# Main_Schematic_ScamAway.net
KiCad netlist of a schematic drawn in EAGLE
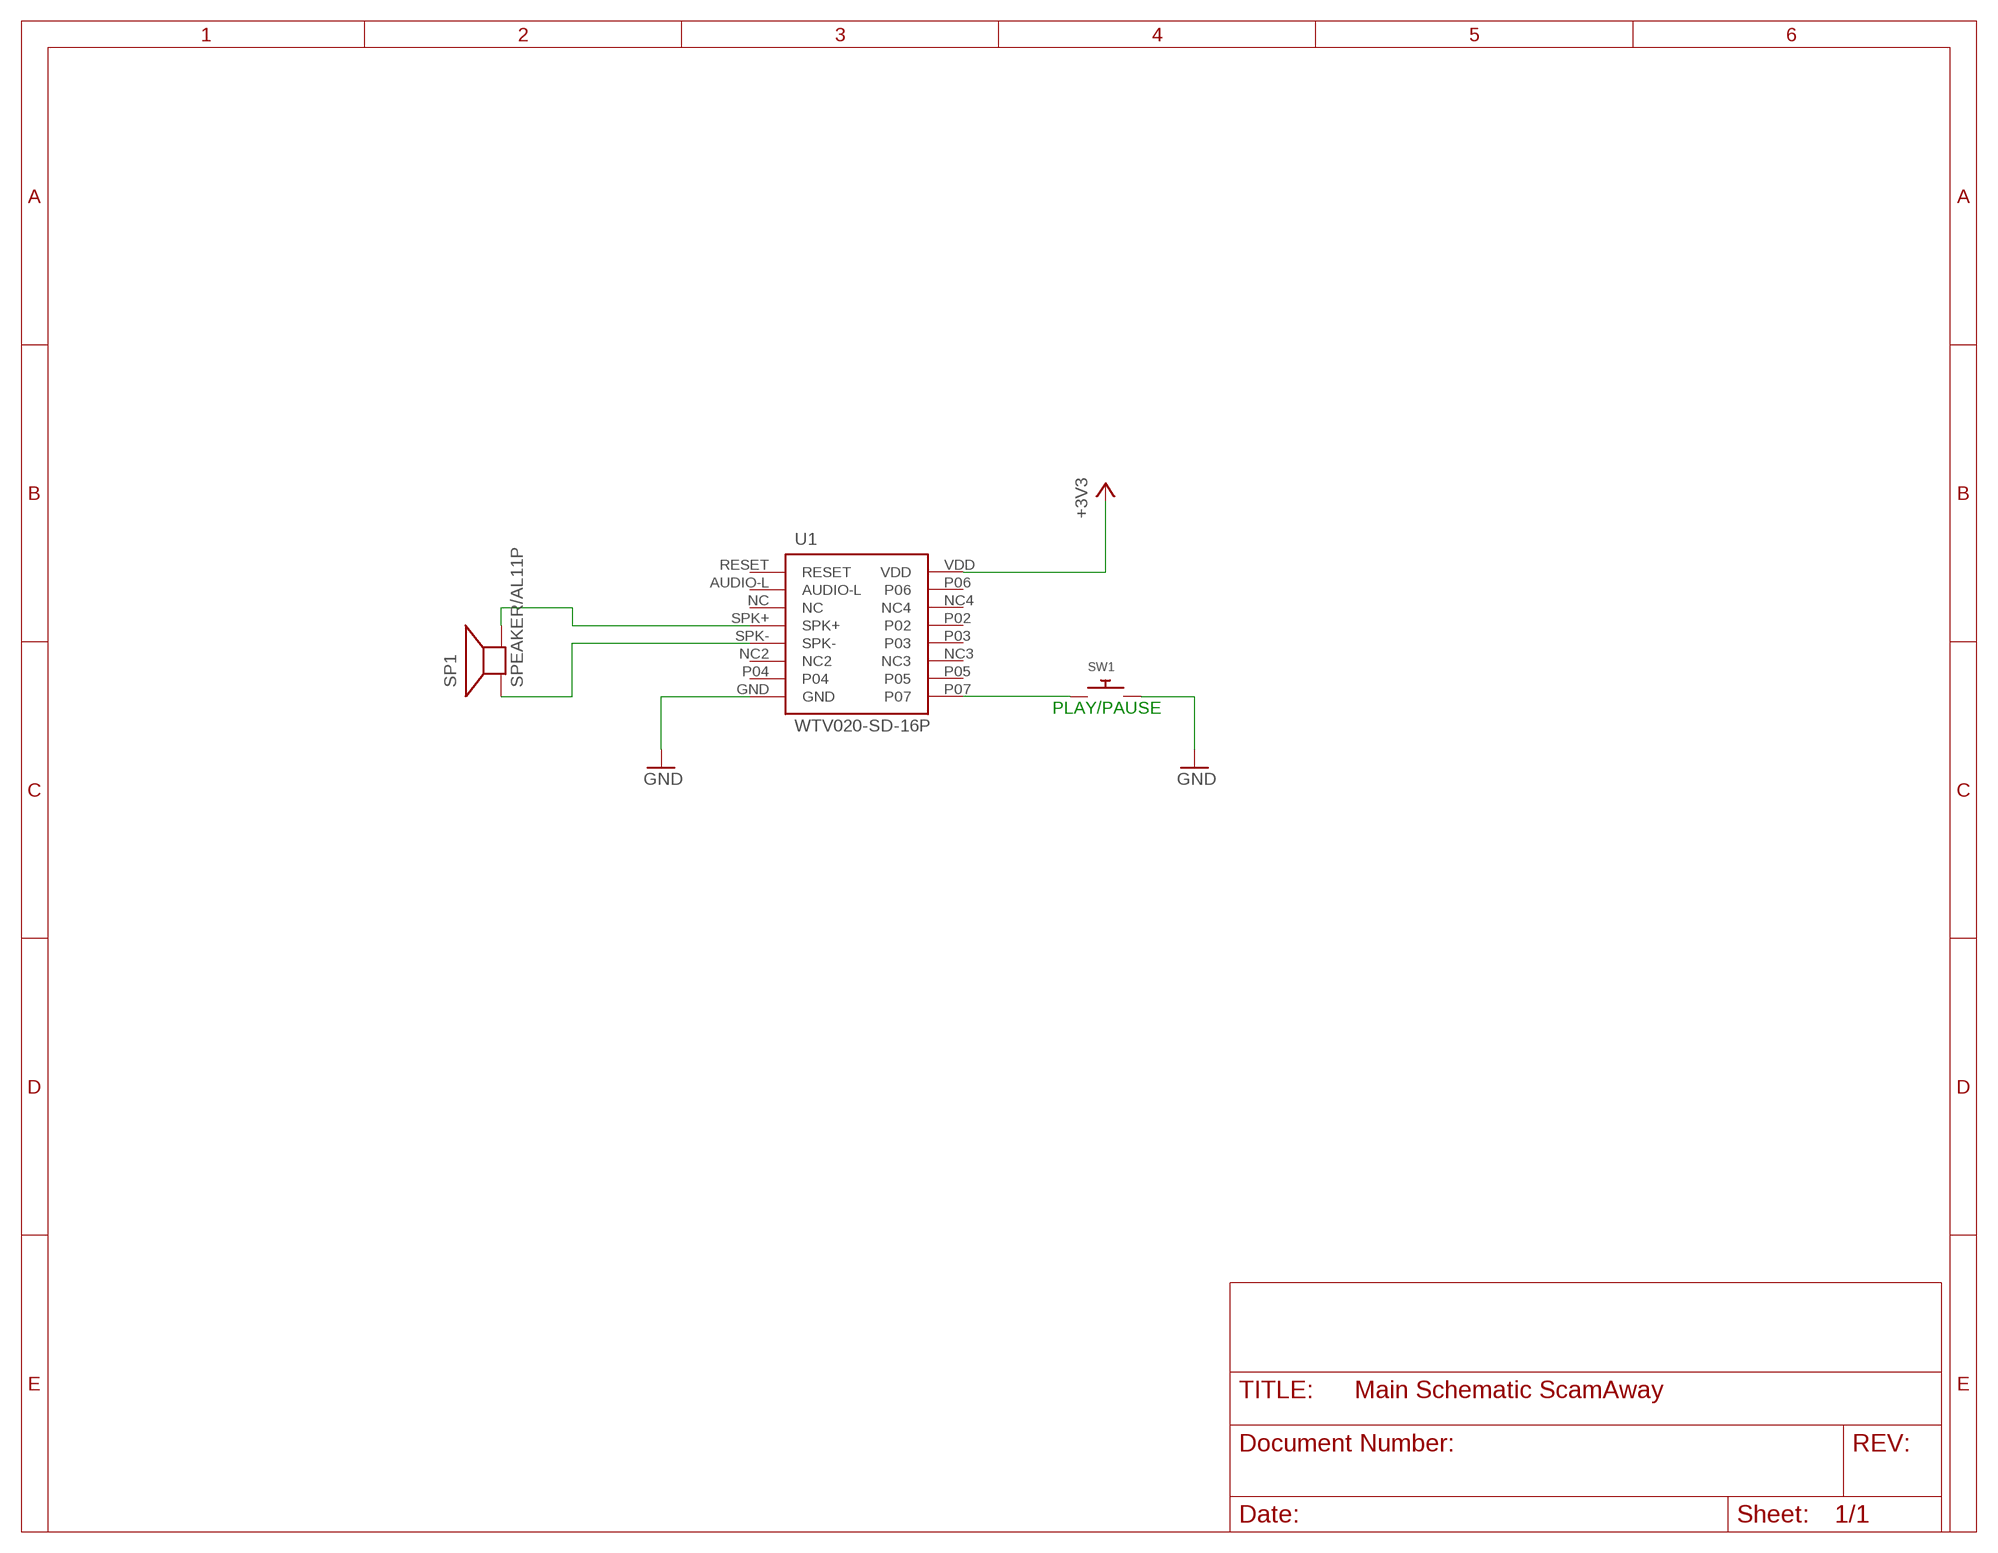
[diagram p0: schematic, sheet 1]

(export (version "E")
  (design (tool "Eeschema 10.0.6"))
  (components
    (comp (ref "SP1")
      (value "SPEAKER/AL11P")
      (footprint "eagle-import:AL11P")
      (libsource (lib "eagle-import") (part "SPEAKER/AL11P"))
    )
    (comp (ref "SW1")
      (value "SWITCH_PUSHBUTTONSOFTTOUCHSMD_SJ")
      (footprint "eagle-import:PUSHBUTTON_SMD_SJ")
      (libsource (lib "eagle-import") (part "SWITCH_PUSHBUTTONSOFTTOUCHSMD_SJ"))
    )
    (comp (ref "U1")
      (value "WTV020-SD-16P")
      (footprint "eagle-import:DIP16")
      (libsource (lib "eagle-import") (part "WTV020-SD-16P"))
    )
  )
  (nets
    (net (code "1") (name "+3V3") (class "Default")
      (node (ref "U1") (pin "VDD") (pinfunction "VDD_VDD") (pintype "power_in"))
    )
    (net (code "2") (name "GND") (class "Default")
      (node (ref "SW1") (pin "P$2") (pinfunction "P$2_P$2") (pintype "passive"))
      (node (ref "U1") (pin "GND") (pinfunction "GND_GND") (pintype "power_in"))
    )
    (net (code "3") (name "Net-(SP1-Pad+)") (class "Default")
      (node (ref "SP1") (pin "+") (pinfunction "+_+") (pintype "passive"))
      (node (ref "U1") (pin "SPK-") (pinfunction "SPK-_SPK-") (pintype "bidirectional"))
    )
    (net (code "4") (name "Net-(SP1-Pad-)") (class "Default")
      (node (ref "SP1") (pin "-") (pinfunction "-_-") (pintype "passive"))
      (node (ref "U1") (pin "SPK+") (pinfunction "SPK+_SPK+") (pintype "bidirectional"))
    )
    (net (code "5") (name "Net-(SW1-PadP$1)") (class "Default")
      (node (ref "SW1") (pin "P$1") (pinfunction "P$1_P$1") (pintype "passive"))
      (node (ref "U1") (pin "P07") (pinfunction "P07_P07") (pintype "bidirectional"))
    )
    (net (code "6") (name "unconnected-(U1-PadAUDIO-L)") (class "Default")
      (node (ref "U1") (pin "AUDIO-L") (pinfunction "AUDIO-L_AUDIO-L") (pintype "bidirectional"))
    )
    (net (code "7") (name "unconnected-(U1-PadNC)") (class "Default")
      (node (ref "U1") (pin "NC") (pinfunction "NC_NC") (pintype "no_connect"))
    )
    (net (code "8") (name "unconnected-(U1-PadNC2)") (class "Default")
      (node (ref "U1") (pin "NC2") (pinfunction "NC2_NC2") (pintype "no_connect"))
    )
    (net (code "9") (name "unconnected-(U1-PadNC3)") (class "Default")
      (node (ref "U1") (pin "NC3") (pinfunction "NC3_NC3") (pintype "no_connect"))
    )
    (net (code "10") (name "unconnected-(U1-PadNC4)") (class "Default")
      (node (ref "U1") (pin "NC4") (pinfunction "NC4_NC4") (pintype "no_connect"))
    )
    (net (code "11") (name "unconnected-(U1-PadP02)") (class "Default")
      (node (ref "U1") (pin "P02") (pinfunction "P02_P02") (pintype "bidirectional"))
    )
    (net (code "12") (name "unconnected-(U1-PadP03)") (class "Default")
      (node (ref "U1") (pin "P03") (pinfunction "P03_P03") (pintype "bidirectional"))
    )
    (net (code "13") (name "unconnected-(U1-PadP04)") (class "Default")
      (node (ref "U1") (pin "P04") (pinfunction "P04_P04") (pintype "bidirectional"))
    )
    (net (code "14") (name "unconnected-(U1-PadP05)") (class "Default")
      (node (ref "U1") (pin "P05") (pinfunction "P05_P05") (pintype "bidirectional"))
    )
    (net (code "15") (name "unconnected-(U1-PadP06)") (class "Default")
      (node (ref "U1") (pin "P06") (pinfunction "P06_P06") (pintype "bidirectional"))
    )
    (net (code "16") (name "unconnected-(U1-PadRESET)") (class "Default")
      (node (ref "U1") (pin "RESET") (pinfunction "RESET_RESET") (pintype "bidirectional"))
    )
  )
)
